# v3.net
KiCad netlist of a schematic drawn in EAGLE
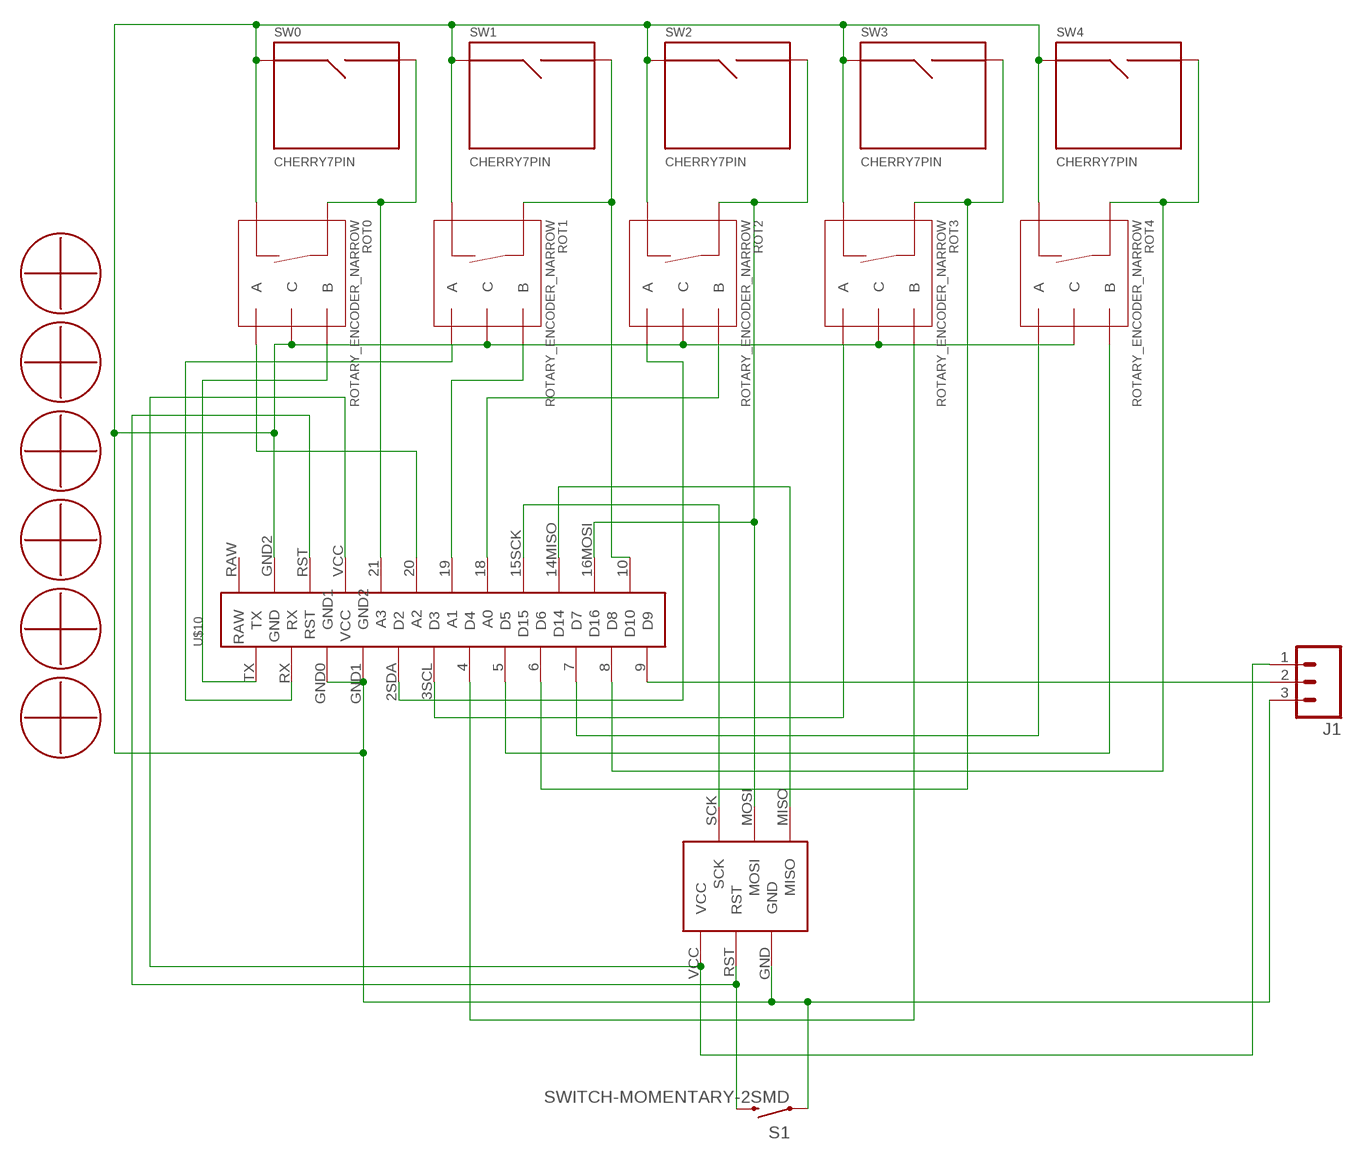
[diagram p0: schematic, sheet 1]

(export (version "E")
  (design (tool "Eeschema 10.0.6"))
  (components
    (comp (ref "J1")
      (value "M031X03_NO_SILK")
      (footprint "eagle-import:1X03_NO_SILK")
      (libsource (lib "eagle-import") (part "M031X03_NO_SILK"))
    )
    (comp (ref "ROT0")
      (value "ROTARY_ENCODER_NARROW")
      (footprint "eagle-import:ROTARY_ENC_NARROW")
      (libsource (lib "eagle-import") (part "ROTARY_ENCODER_NARROW"))
    )
    (comp (ref "ROT1")
      (value "ROTARY_ENCODER_NARROW")
      (footprint "eagle-import:ROTARY_ENC_NARROW")
      (libsource (lib "eagle-import") (part "ROTARY_ENCODER_NARROW"))
    )
    (comp (ref "ROT2")
      (value "ROTARY_ENCODER_NARROW")
      (footprint "eagle-import:ROTARY_ENC_NARROW")
      (libsource (lib "eagle-import") (part "ROTARY_ENCODER_NARROW"))
    )
    (comp (ref "ROT3")
      (value "ROTARY_ENCODER_NARROW")
      (footprint "eagle-import:ROTARY_ENC_NARROW")
      (libsource (lib "eagle-import") (part "ROTARY_ENCODER_NARROW"))
    )
    (comp (ref "ROT4")
      (value "ROTARY_ENCODER_NARROW")
      (footprint "eagle-import:ROTARY_ENC_NARROW")
      (libsource (lib "eagle-import") (part "ROTARY_ENCODER_NARROW"))
    )
    (comp (ref "S1")
      (value "SWITCH-MOMENTARY-2SMD")
      (footprint "eagle-import:TACTILE_SWITCH_SMD")
      (libsource (lib "eagle-import") (part "SWITCH-MOMENTARY-2SMD"))
    )
    (comp (ref "SW0")
      (value "CHERRY7PIN")
      (footprint "eagle-import:CHERRY5HOLE")
      (libsource (lib "eagle-import") (part "CHERRY7PIN"))
    )
    (comp (ref "SW1")
      (value "CHERRY7PIN")
      (footprint "eagle-import:CHERRY5HOLE")
      (libsource (lib "eagle-import") (part "CHERRY7PIN"))
    )
    (comp (ref "SW2")
      (value "CHERRY7PIN")
      (footprint "eagle-import:CHERRY5HOLE")
      (libsource (lib "eagle-import") (part "CHERRY7PIN"))
    )
    (comp (ref "SW3")
      (value "CHERRY7PIN")
      (footprint "eagle-import:CHERRY5HOLE")
      (libsource (lib "eagle-import") (part "CHERRY7PIN"))
    )
    (comp (ref "SW4")
      (value "CHERRY7PIN")
      (footprint "eagle-import:CHERRY5HOLE")
      (libsource (lib "eagle-import") (part "CHERRY7PIN"))
    )
    (comp (ref "U$1")
      (value "ICSP")
      (footprint "eagle-import:ICSP")
      (libsource (lib "eagle-import") (part "ICSP"))
    )
    (comp (ref "U$6")
      (value "M2MOUNT")
      (footprint "eagle-import:M2MOUNT")
      (libsource (lib "eagle-import") (part "M2MOUNT"))
    )
    (comp (ref "U$10")
      (value "PROMICROLOCK")
      (footprint "eagle-import:PROMICRO-LOCK")
      (libsource (lib "eagle-import") (part "PROMICROLOCK"))
    )
    (comp (ref "U$11")
      (value "M2MOUNT")
      (footprint "eagle-import:M2MOUNT")
      (libsource (lib "eagle-import") (part "M2MOUNT"))
    )
    (comp (ref "U$12")
      (value "M2MOUNT")
      (footprint "eagle-import:M2MOUNT")
      (libsource (lib "eagle-import") (part "M2MOUNT"))
    )
    (comp (ref "U$13")
      (value "M2MOUNT")
      (footprint "eagle-import:M2MOUNT")
      (libsource (lib "eagle-import") (part "M2MOUNT"))
    )
    (comp (ref "U$15")
      (value "M2MOUNT")
      (footprint "eagle-import:M2MOUNT")
      (libsource (lib "eagle-import") (part "M2MOUNT"))
    )
    (comp (ref "U$17")
      (value "M2MOUNT")
      (footprint "eagle-import:M2MOUNT")
      (libsource (lib "eagle-import") (part "M2MOUNT"))
    )
  )
  (nets
    (net (code "1") (name "Net-(J1-Pad1)") (class "Default")
      (node (ref "J1") (pin "1") (pinfunction "1_1") (pintype "passive"))
      (node (ref "U$1") (pin "VCC") (pinfunction "VCC_VCC") (pintype "bidirectional"))
      (node (ref "U$10") (pin "VCC") (pinfunction "VCC_VCC") (pintype "bidirectional"))
    )
    (net (code "2") (name "Net-(ROT0-PadB)") (class "Default")
      (node (ref "ROT0") (pin "B") (pinfunction "B_B") (pintype "bidirectional"))
      (node (ref "U$10") (pin "TX") (pinfunction "TX_TX") (pintype "bidirectional"))
    )
    (net (code "3") (name "Net-(ROT1-PadA)") (class "Default")
      (node (ref "ROT1") (pin "A") (pinfunction "A_A") (pintype "bidirectional"))
      (node (ref "U$10") (pin "RX") (pinfunction "RX_RX") (pintype "bidirectional"))
    )
    (net (code "4") (name "Net-(S1-2)") (class "Default")
      (node (ref "S1") (pin "3") (pinfunction "2_3") (pintype "passive"))
      (node (ref "U$1") (pin "RST") (pinfunction "RST_RST") (pintype "bidirectional"))
      (node (ref "U$10") (pin "RST") (pinfunction "RST_RST") (pintype "bidirectional"))
    )
    (net (code "5") (name "Net-(SW0-SIG1)") (class "Default")
      (node (ref "J1") (pin "3") (pinfunction "3_3") (pintype "passive"))
      (node (ref "ROT0") (pin "C") (pinfunction "C_C") (pintype "bidirectional"))
      (node (ref "ROT0") (pin "SW-") (pinfunction "SW-_SW-") (pintype "bidirectional"))
      (node (ref "ROT1") (pin "C") (pinfunction "C_C") (pintype "bidirectional"))
      (node (ref "ROT1") (pin "SW-") (pinfunction "SW-_SW-") (pintype "bidirectional"))
      (node (ref "ROT2") (pin "C") (pinfunction "C_C") (pintype "bidirectional"))
      (node (ref "ROT2") (pin "SW-") (pinfunction "SW-_SW-") (pintype "bidirectional"))
      (node (ref "ROT3") (pin "C") (pinfunction "C_C") (pintype "bidirectional"))
      (node (ref "ROT3") (pin "SW-") (pinfunction "SW-_SW-") (pintype "bidirectional"))
      (node (ref "ROT4") (pin "C") (pinfunction "C_C") (pintype "bidirectional"))
      (node (ref "ROT4") (pin "SW-") (pinfunction "SW-_SW-") (pintype "bidirectional"))
      (node (ref "S1") (pin "1") (pinfunction "1_1") (pintype "passive"))
      (node (ref "SW0") (pin "P$1") (pinfunction "SIG1_P$1") (pintype "bidirectional"))
      (node (ref "SW1") (pin "P$1") (pinfunction "SIG1_P$1") (pintype "bidirectional"))
      (node (ref "SW2") (pin "P$1") (pinfunction "SIG1_P$1") (pintype "bidirectional"))
      (node (ref "SW3") (pin "P$1") (pinfunction "SIG1_P$1") (pintype "bidirectional"))
      (node (ref "SW4") (pin "P$1") (pinfunction "SIG1_P$1") (pintype "bidirectional"))
      (node (ref "U$1") (pin "GND") (pinfunction "GND_GND") (pintype "bidirectional"))
      (node (ref "U$10") (pin "GND0") (pinfunction "GND1_GND0") (pintype "bidirectional"))
      (node (ref "U$10") (pin "GND1") (pinfunction "GND2_GND1") (pintype "bidirectional"))
      (node (ref "U$10") (pin "GND2") (pinfunction "GND_GND2") (pintype "bidirectional"))
    )
    (net (code "6") (name "Net-(SW0-SIG2)") (class "Default")
      (node (ref "ROT0") (pin "SW+") (pinfunction "SW+_SW+") (pintype "bidirectional"))
      (node (ref "SW0") (pin "P$2") (pinfunction "SIG2_P$2") (pintype "bidirectional"))
      (node (ref "U$10") (pin "21") (pinfunction "A3_21") (pintype "bidirectional"))
    )
    (net (code "7") (name "Net-(SW1-SIG2)") (class "Default")
      (node (ref "ROT1") (pin "SW+") (pinfunction "SW+_SW+") (pintype "bidirectional"))
      (node (ref "SW1") (pin "P$2") (pinfunction "SIG2_P$2") (pintype "bidirectional"))
      (node (ref "U$10") (pin "10") (pinfunction "D10_10") (pintype "bidirectional"))
    )
    (net (code "8") (name "Net-(SW2-SIG2)") (class "Default")
      (node (ref "ROT2") (pin "SW+") (pinfunction "SW+_SW+") (pintype "bidirectional"))
      (node (ref "SW2") (pin "P$2") (pinfunction "SIG2_P$2") (pintype "bidirectional"))
      (node (ref "U$1") (pin "MOSI") (pinfunction "MOSI_MOSI") (pintype "bidirectional"))
      (node (ref "U$10") (pin "16MOSI") (pinfunction "D16_16MOSI") (pintype "bidirectional"))
    )
    (net (code "9") (name "Net-(SW3-SIG2)") (class "Default")
      (node (ref "ROT3") (pin "SW+") (pinfunction "SW+_SW+") (pintype "bidirectional"))
      (node (ref "SW3") (pin "P$2") (pinfunction "SIG2_P$2") (pintype "bidirectional"))
      (node (ref "U$10") (pin "6") (pinfunction "D6_6") (pintype "bidirectional"))
    )
    (net (code "10") (name "Net-(SW4-SIG2)") (class "Default")
      (node (ref "ROT4") (pin "SW+") (pinfunction "SW+_SW+") (pintype "bidirectional"))
      (node (ref "SW4") (pin "P$2") (pinfunction "SIG2_P$2") (pintype "bidirectional"))
      (node (ref "U$10") (pin "8") (pinfunction "D8_8") (pintype "bidirectional"))
    )
    (net (code "11") (name "Net-(U$10-A0)") (class "Default")
      (node (ref "ROT2") (pin "B") (pinfunction "B_B") (pintype "bidirectional"))
      (node (ref "U$10") (pin "18") (pinfunction "A0_18") (pintype "bidirectional"))
    )
    (net (code "12") (name "Net-(U$10-A1)") (class "Default")
      (node (ref "ROT1") (pin "B") (pinfunction "B_B") (pintype "bidirectional"))
      (node (ref "U$10") (pin "19") (pinfunction "A1_19") (pintype "bidirectional"))
    )
    (net (code "13") (name "Net-(U$10-A2)") (class "Default")
      (node (ref "ROT0") (pin "A") (pinfunction "A_A") (pintype "bidirectional"))
      (node (ref "U$10") (pin "20") (pinfunction "A2_20") (pintype "bidirectional"))
    )
    (net (code "14") (name "Net-(U$10-D2)") (class "Default")
      (node (ref "ROT2") (pin "A") (pinfunction "A_A") (pintype "bidirectional"))
      (node (ref "U$10") (pin "2SDA") (pinfunction "D2_2SDA") (pintype "bidirectional"))
    )
    (net (code "15") (name "Net-(U$10-D3)") (class "Default")
      (node (ref "ROT3") (pin "A") (pinfunction "A_A") (pintype "bidirectional"))
      (node (ref "U$10") (pin "3SCL") (pinfunction "D3_3SCL") (pintype "bidirectional"))
    )
    (net (code "16") (name "Net-(U$10-D4)") (class "Default")
      (node (ref "ROT3") (pin "B") (pinfunction "B_B") (pintype "bidirectional"))
      (node (ref "U$10") (pin "4") (pinfunction "D4_4") (pintype "bidirectional"))
    )
    (net (code "17") (name "Net-(U$10-D5)") (class "Default")
      (node (ref "ROT4") (pin "B") (pinfunction "B_B") (pintype "bidirectional"))
      (node (ref "U$10") (pin "5") (pinfunction "D5_5") (pintype "bidirectional"))
    )
    (net (code "18") (name "Net-(U$10-D7)") (class "Default")
      (node (ref "ROT4") (pin "A") (pinfunction "A_A") (pintype "bidirectional"))
      (node (ref "U$10") (pin "7") (pinfunction "D7_7") (pintype "bidirectional"))
    )
    (net (code "19") (name "Net-(U$10-D9)") (class "Default")
      (node (ref "J1") (pin "2") (pinfunction "2_2") (pintype "passive"))
      (node (ref "U$10") (pin "9") (pinfunction "D9_9") (pintype "bidirectional"))
    )
    (net (code "20") (name "Net-(U$10-D14)") (class "Default")
      (node (ref "U$1") (pin "MISO") (pinfunction "MISO_MISO") (pintype "bidirectional"))
      (node (ref "U$10") (pin "14MISO") (pinfunction "D14_14MISO") (pintype "bidirectional"))
    )
    (net (code "21") (name "Net-(U$10-D15)") (class "Default")
      (node (ref "U$1") (pin "SCK") (pinfunction "SCK_SCK") (pintype "bidirectional"))
      (node (ref "U$10") (pin "15SCK") (pinfunction "D15_15SCK") (pintype "bidirectional"))
    )
    (net (code "22") (name "unconnected-(U$10-PadRAW)") (class "Default")
      (node (ref "U$10") (pin "RAW") (pinfunction "RAW_RAW") (pintype "bidirectional"))
    )
  )
)
